# 03cpu_sodimm.net
KiCad netlist of a schematic drawn in Altium Designer
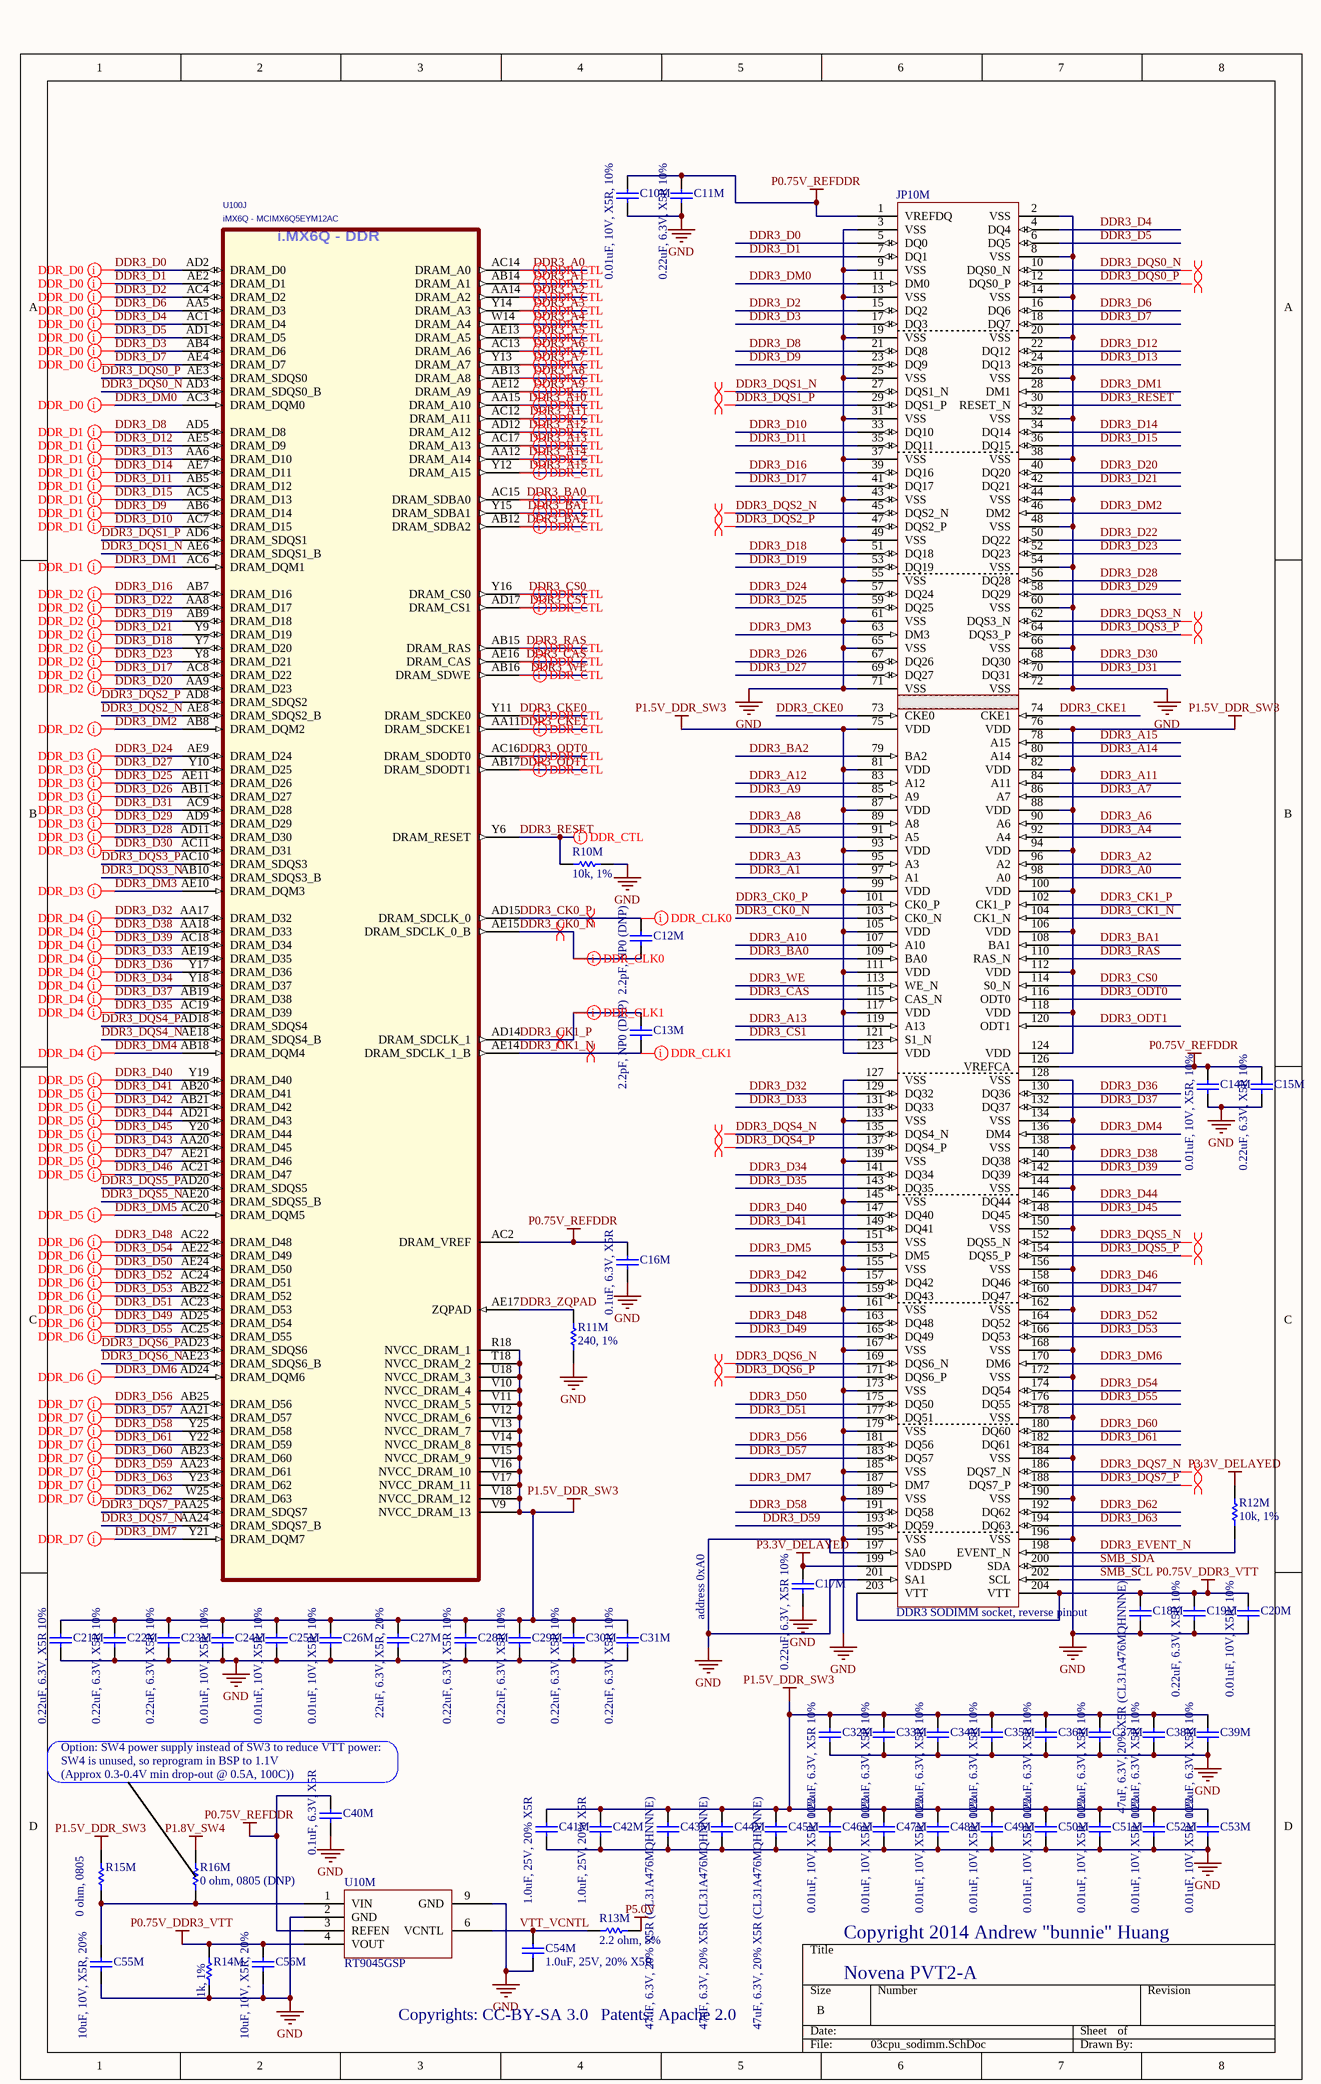
[diagram p0: 03cpu_sodimm.SchDoc]

(export (version "E")
  (design (tool "Eeschema 10.0.6"))
  (components
    (comp (ref "C10M")
      (value "0.01uF, 10V, X5R, 10%")
      (footprint "CAPC0603N_B")
      (description "Capacitor (Semiconductor SIM Model)")
      (fields (field (name "PUBLISHER") "Altium Limited"))
      (libsource (lib "Miscellaneous Devices") (part "Cap Semi"))
    )
    (comp (ref "C11M")
      (value "0.22uF, 6.3V, X5R 10%")
      (footprint "CAPC0603N_B")
      (description "CAP CER 0.22UF 6.3V 20% X5R 0201")
      (fields (field (name "PUBLISHER") "Altium Limited"))
      (libsource (lib "Miscellaneous Devices") (part "Cap Semi"))
    )
    (comp (ref "C12M")
      (value "2.2pF, NP0 (DNP)")
      (footprint "CAPC1005N")
      (description "Capacitor (Semiconductor SIM Model)")
      (fields (field (name "PUBLISHER") "Altium Limited"))
      (libsource (lib "Miscellaneous Devices") (part "Cap Semi"))
    )
    (comp (ref "C13M")
      (value "2.2pF, NP0 (DNP)")
      (footprint "CAPC1005N")
      (description "Capacitor (Semiconductor SIM Model)")
      (fields (field (name "PUBLISHER") "Altium Limited"))
      (libsource (lib "Miscellaneous Devices") (part "Cap Semi"))
    )
    (comp (ref "C14M")
      (value "0.01uF, 10V, X5R, 10%")
      (footprint "CAPC0603N_B")
      (description "Capacitor (Semiconductor SIM Model)")
      (fields (field (name "PUBLISHER") "Altium Limited"))
      (libsource (lib "Miscellaneous Devices") (part "Cap Semi"))
    )
    (comp (ref "C15M")
      (value "0.22uF, 6.3V, X5R 10%")
      (footprint "CAPC0603N_B")
      (description "CAP CER 0.22UF 6.3V 20% X5R 0201")
      (fields (field (name "PUBLISHER") "Altium Limited"))
      (libsource (lib "Miscellaneous Devices") (part "Cap Semi"))
    )
    (comp (ref "C16M")
      (value "0.1uF, 6.3V, X5R")
      (footprint "CAPC0603N_B")
      (description "Capacitor (Semiconductor SIM Model)")
      (fields (field (name "PUBLISHER") "Altium Limited"))
      (libsource (lib "Miscellaneous Devices") (part "Cap Semi"))
    )
    (comp (ref "C17M")
      (value "0.22uF, 6.3V, X5R 10%")
      (footprint "CAPC0603N_B")
      (description "CAP CER 0.22UF 6.3V 20% X5R 0201")
      (fields (field (name "PUBLISHER") "Altium Limited"))
      (libsource (lib "Miscellaneous Devices") (part "Cap Semi"))
    )
    (comp (ref "C18M")
      (value "47uF, 6.3V, 20% X5R (CL31A476MQHNNNE)")
      (footprint "CAPC3216N")
      (description "Capacitor (Semiconductor SIM Model)")
      (fields (field (name "PUBLISHER") "Altium Limited"))
      (libsource (lib "Miscellaneous Devices") (part "Cap Semi"))
    )
    (comp (ref "C19M")
      (value "0.22uF, 6.3V, X5R 10%")
      (footprint "CAPC0603N_B")
      (description "CAP CER 0.22UF 6.3V 20% X5R 0201")
      (fields (field (name "PUBLISHER") "Altium Limited"))
      (libsource (lib "Miscellaneous Devices") (part "Cap Semi"))
    )
    (comp (ref "C20M")
      (value "0.01uF, 10V, X5R, 10%")
      (footprint "CAPC0603N_B")
      (description "Capacitor (Semiconductor SIM Model)")
      (fields (field (name "PUBLISHER") "Altium Limited"))
      (libsource (lib "Miscellaneous Devices") (part "Cap Semi"))
    )
    (comp (ref "C21M")
      (value "0.22uF, 6.3V, X5R 10%")
      (footprint "CAPC0603N_B")
      (description "CAP CER 0.22UF 6.3V 20% X5R 0201")
      (fields (field (name "PUBLISHER") "Altium Limited"))
      (libsource (lib "Miscellaneous Devices") (part "Cap Semi"))
    )
    (comp (ref "C22M")
      (value "0.22uF, 6.3V, X5R 10%")
      (footprint "CAPC0603N_B")
      (description "CAP CER 0.22UF 6.3V 20% X5R 0201")
      (fields (field (name "PUBLISHER") "Altium Limited"))
      (libsource (lib "Miscellaneous Devices") (part "Cap Semi"))
    )
    (comp (ref "C23M")
      (value "0.22uF, 6.3V, X5R 10%")
      (footprint "CAPC0603N_B")
      (description "CAP CER 0.22UF 6.3V 20% X5R 0201")
      (fields (field (name "PUBLISHER") "Altium Limited"))
      (libsource (lib "Miscellaneous Devices") (part "Cap Semi"))
    )
    (comp (ref "C24M")
      (value "0.01uF, 10V, X5R, 10%")
      (footprint "CAPC0603N_B")
      (description "Capacitor (Semiconductor SIM Model)")
      (fields (field (name "PUBLISHER") "Altium Limited"))
      (libsource (lib "Miscellaneous Devices") (part "Cap Semi"))
    )
    (comp (ref "C25M")
      (value "0.01uF, 10V, X5R, 10%")
      (footprint "CAPC0603N_B")
      (description "Capacitor (Semiconductor SIM Model)")
      (fields (field (name "PUBLISHER") "Altium Limited"))
      (libsource (lib "Miscellaneous Devices") (part "Cap Semi"))
    )
    (comp (ref "C26M")
      (value "0.01uF, 10V, X5R, 10%")
      (footprint "CAPC0603N_B")
      (description "Capacitor (Semiconductor SIM Model)")
      (fields (field (name "PUBLISHER") "Altium Limited"))
      (libsource (lib "Miscellaneous Devices") (part "Cap Semi"))
    )
    (comp (ref "C27M")
      (value "22uF, 6.3V, X5R, 20%")
      (footprint "CAPC1608N_HD")
      (description "Capacitor (Semiconductor SIM Model)")
      (fields (field (name "PUBLISHER") "Altium Limited"))
      (libsource (lib "Miscellaneous Devices") (part "Cap Semi"))
    )
    (comp (ref "C28M")
      (value "0.22uF, 6.3V, X5R 10%")
      (footprint "CAPC0603N_B")
      (description "CAP CER 0.22UF 6.3V 20% X5R 0201")
      (fields (field (name "PUBLISHER") "Altium Limited"))
      (libsource (lib "Miscellaneous Devices") (part "Cap Semi"))
    )
    (comp (ref "C29M")
      (value "0.22uF, 6.3V, X5R 10%")
      (footprint "CAPC0603N_B")
      (description "CAP CER 0.22UF 6.3V 20% X5R 0201")
      (fields (field (name "PUBLISHER") "Altium Limited"))
      (libsource (lib "Miscellaneous Devices") (part "Cap Semi"))
    )
    (comp (ref "C30M")
      (value "0.22uF, 6.3V, X5R 10%")
      (footprint "CAPC0603N_B")
      (description "CAP CER 0.22UF 6.3V 20% X5R 0201")
      (fields (field (name "PUBLISHER") "Altium Limited"))
      (libsource (lib "Miscellaneous Devices") (part "Cap Semi"))
    )
    (comp (ref "C31M")
      (value "0.22uF, 6.3V, X5R 10%")
      (footprint "CAPC0603N_B")
      (description "CAP CER 0.22UF 6.3V 20% X5R 0201")
      (fields (field (name "PUBLISHER") "Altium Limited"))
      (libsource (lib "Miscellaneous Devices") (part "Cap Semi"))
    )
    (comp (ref "C32M")
      (value "0.22uF, 6.3V, X5R 10%")
      (footprint "CAPC0603N_B")
      (description "CAP CER 0.22UF 6.3V 20% X5R 0201")
      (fields (field (name "PUBLISHER") "Altium Limited"))
      (libsource (lib "Miscellaneous Devices") (part "Cap Semi"))
    )
    (comp (ref "C33M")
      (value "0.22uF, 6.3V, X5R 10%")
      (footprint "CAPC0603N_B")
      (description "CAP CER 0.22UF 6.3V 20% X5R 0201")
      (fields (field (name "PUBLISHER") "Altium Limited"))
      (libsource (lib "Miscellaneous Devices") (part "Cap Semi"))
    )
    (comp (ref "C34M")
      (value "0.22uF, 6.3V, X5R 10%")
      (footprint "CAPC0603N_B")
      (description "CAP CER 0.22UF 6.3V 20% X5R 0201")
      (fields (field (name "PUBLISHER") "Altium Limited"))
      (libsource (lib "Miscellaneous Devices") (part "Cap Semi"))
    )
    (comp (ref "C35M")
      (value "0.22uF, 6.3V, X5R 10%")
      (footprint "CAPC0603N_B")
      (description "CAP CER 0.22UF 6.3V 20% X5R 0201")
      (fields (field (name "PUBLISHER") "Altium Limited"))
      (libsource (lib "Miscellaneous Devices") (part "Cap Semi"))
    )
    (comp (ref "C36M")
      (value "0.22uF, 6.3V, X5R 10%")
      (footprint "CAPC0603N_B")
      (description "CAP CER 0.22UF 6.3V 20% X5R 0201")
      (fields (field (name "PUBLISHER") "Altium Limited"))
      (libsource (lib "Miscellaneous Devices") (part "Cap Semi"))
    )
    (comp (ref "C37M")
      (value "0.22uF, 6.3V, X5R 10%")
      (footprint "CAPC0603N_B")
      (description "CAP CER 0.22UF 6.3V 20% X5R 0201")
      (fields (field (name "PUBLISHER") "Altium Limited"))
      (libsource (lib "Miscellaneous Devices") (part "Cap Semi"))
    )
    (comp (ref "C38M")
      (value "0.22uF, 6.3V, X5R 10%")
      (footprint "CAPC0603N_B")
      (description "CAP CER 0.22UF 6.3V 20% X5R 0201")
      (fields (field (name "PUBLISHER") "Altium Limited"))
      (libsource (lib "Miscellaneous Devices") (part "Cap Semi"))
    )
    (comp (ref "C39M")
      (value "0.22uF, 6.3V, X5R 10%")
      (footprint "CAPC0603N_B")
      (description "CAP CER 0.22UF 6.3V 20% X5R 0201")
      (fields (field (name "PUBLISHER") "Altium Limited"))
      (libsource (lib "Miscellaneous Devices") (part "Cap Semi"))
    )
    (comp (ref "C40M")
      (value "0.1uF, 6.3V, X5R")
      (footprint "CAPC0603N_B")
      (description "Capacitor (Semiconductor SIM Model)")
      (fields (field (name "PUBLISHER") "Altium Limited"))
      (libsource (lib "Miscellaneous Devices") (part "Cap Semi"))
    )
    (comp (ref "C41M")
      (value "1.0uF, 25V, 20% X5R")
      (footprint "CAPC1608N")
      (description "Capacitor (Semiconductor SIM Model)")
      (fields (field (name "PUBLISHER") "Altium Limited"))
      (libsource (lib "Miscellaneous Devices") (part "Cap Semi"))
    )
    (comp (ref "C42M")
      (value "1.0uF, 25V, 20% X5R")
      (footprint "CAPC1608N")
      (description "Capacitor (Semiconductor SIM Model)")
      (fields (field (name "PUBLISHER") "Altium Limited"))
      (libsource (lib "Miscellaneous Devices") (part "Cap Semi"))
    )
    (comp (ref "C43M")
      (value "47uF, 6.3V, 20% X5R (CL31A476MQHNNNE)")
      (footprint "CAPC3216N")
      (description "Capacitor (Semiconductor SIM Model)")
      (fields (field (name "PUBLISHER") "Altium Limited"))
      (libsource (lib "Miscellaneous Devices") (part "Cap Semi"))
    )
    (comp (ref "C44M")
      (value "47uF, 6.3V, 20% X5R (CL31A476MQHNNNE)")
      (footprint "CAPC3216N")
      (description "Capacitor (Semiconductor SIM Model)")
      (fields (field (name "PUBLISHER") "Altium Limited"))
      (libsource (lib "Miscellaneous Devices") (part "Cap Semi"))
    )
    (comp (ref "C45M")
      (value "47uF, 6.3V, 20% X5R (CL31A476MQHNNNE)")
      (footprint "CAPC3216N")
      (description "Capacitor (Semiconductor SIM Model)")
      (fields (field (name "PUBLISHER") "Altium Limited"))
      (libsource (lib "Miscellaneous Devices") (part "Cap Semi"))
    )
    (comp (ref "C46M")
      (value "0.01uF, 10V, X5R, 10%")
      (footprint "CAPC0603N_B")
      (description "Capacitor (Semiconductor SIM Model)")
      (fields (field (name "PUBLISHER") "Altium Limited"))
      (libsource (lib "Miscellaneous Devices") (part "Cap Semi"))
    )
    (comp (ref "C47M")
      (value "0.01uF, 10V, X5R, 10%")
      (footprint "CAPC0603N_B")
      (description "Capacitor (Semiconductor SIM Model)")
      (fields (field (name "PUBLISHER") "Altium Limited"))
      (libsource (lib "Miscellaneous Devices") (part "Cap Semi"))
    )
    (comp (ref "C48M")
      (value "0.01uF, 10V, X5R, 10%")
      (footprint "CAPC0603N_B")
      (description "Capacitor (Semiconductor SIM Model)")
      (fields (field (name "PUBLISHER") "Altium Limited"))
      (libsource (lib "Miscellaneous Devices") (part "Cap Semi"))
    )
    (comp (ref "C49M")
      (value "0.01uF, 10V, X5R, 10%")
      (footprint "CAPC0603N_B")
      (description "Capacitor (Semiconductor SIM Model)")
      (fields (field (name "PUBLISHER") "Altium Limited"))
      (libsource (lib "Miscellaneous Devices") (part "Cap Semi"))
    )
    (comp (ref "C50M")
      (value "0.01uF, 10V, X5R, 10%")
      (footprint "CAPC0603N_B")
      (description "Capacitor (Semiconductor SIM Model)")
      (fields (field (name "PUBLISHER") "Altium Limited"))
      (libsource (lib "Miscellaneous Devices") (part "Cap Semi"))
    )
    (comp (ref "C51M")
      (value "0.01uF, 10V, X5R, 10%")
      (footprint "CAPC0603N_B")
      (description "Capacitor (Semiconductor SIM Model)")
      (fields (field (name "PUBLISHER") "Altium Limited"))
      (libsource (lib "Miscellaneous Devices") (part "Cap Semi"))
    )
    (comp (ref "C52M")
      (value "0.01uF, 10V, X5R, 10%")
      (footprint "CAPC0603N_B")
      (description "Capacitor (Semiconductor SIM Model)")
      (fields (field (name "PUBLISHER") "Altium Limited"))
      (libsource (lib "Miscellaneous Devices") (part "Cap Semi"))
    )
    (comp (ref "C53M")
      (value "0.01uF, 10V, X5R, 10%")
      (footprint "CAPC0603N_B")
      (description "Capacitor (Semiconductor SIM Model)")
      (fields (field (name "PUBLISHER") "Altium Limited"))
      (libsource (lib "Miscellaneous Devices") (part "Cap Semi"))
    )
    (comp (ref "C54M")
      (value "1.0uF, 25V, 20% X5R")
      (footprint "CAPC1608N")
      (description "Capacitor (Semiconductor SIM Model)")
      (fields (field (name "PUBLISHER") "Altium Limited"))
      (libsource (lib "Miscellaneous Devices") (part "Cap Semi"))
    )
    (comp (ref "C55M")
      (value "10uF, 10V, X5R, 20%")
      (footprint "CAPC1608N")
      (description "Capacitor (Semiconductor SIM Model)")
      (fields (field (name "PUBLISHER") "Altium Limited"))
      (libsource (lib "Miscellaneous Devices") (part "Cap Semi"))
    )
    (comp (ref "C56M")
      (value "10uF, 10V, X5R, 20%")
      (footprint "CAPC1608N")
      (description "Capacitor (Semiconductor SIM Model)")
      (fields (field (name "PUBLISHER") "Altium Limited"))
      (libsource (lib "Miscellaneous Devices") (part "Cap Semi"))
    )
    (comp (ref "JP10M")
      (value "DDR3 SODIMM socket, reverse pinout")
      (footprint "DDR3_SODIMM_REV")
      (description "TE Connectivity 2013311 or equiv (9.2mm height)")
      (libsource (lib "commonsch") (part "DDR3_SODIMM"))
    )
    (comp (ref "R10M")
      (value "10k, 1%")
      (footprint "RESC1005N")
      (description "Resistor")
      (fields (field (name "PUBLISHER") "Altium Limited"))
      (libsource (lib "Miscellaneous Devices") (part "Res1"))
    )
    (comp (ref "R11M")
      (value "240, 1%")
      (footprint "RESC1005N")
      (description "Resistor")
      (fields (field (name "PUBLISHER") "Altium Limited"))
      (libsource (lib "Miscellaneous Devices") (part "Res1"))
    )
    (comp (ref "R12M")
      (value "10k, 1%")
      (footprint "RESC1005N")
      (description "Resistor")
      (fields (field (name "PUBLISHER") "Altium Limited"))
      (libsource (lib "Miscellaneous Devices") (part "Res1"))
    )
    (comp (ref "R13M")
      (value "2.2 ohm, 5%")
      (footprint "RESC1005N")
      (description "Resistor")
      (fields (field (name "PUBLISHER") "Altium Limited"))
      (libsource (lib "Miscellaneous Devices") (part "Res1"))
    )
    (comp (ref "R14M")
      (value "1k, 1%")
      (footprint "RESC1005N")
      (description "Resistor")
      (fields (field (name "PUBLISHER") "Altium Limited"))
      (libsource (lib "Miscellaneous Devices") (part "Res1"))
    )
    (comp (ref "R15M")
      (value "0 ohm, 0805")
      (footprint "RESC2012N")
      (description "Resistor")
      (fields (field (name "PUBLISHER") "Altium Limited"))
      (libsource (lib "Miscellaneous Devices") (part "Res1"))
    )
    (comp (ref "R16M")
      (value "0 ohm, 0805 (DNP)")
      (footprint "RESC2012N")
      (description "Resistor")
      (fields (field (name "PUBLISHER") "Altium Limited"))
      (libsource (lib "Miscellaneous Devices") (part "Res1"))
    )
    (comp (ref "U10M")
      (value "RT9045GSP")
      (footprint "SOIC127P600_HS-8N")
      (description "1.8A sink/source bus termination regulator (VTT)")
      (libsource (lib "commonsch") (part "RT9045GSP"))
    )
    (comp (ref "U100")
      (value "iMX6Q - MCIMX6Q5EYM12AC")
      (description "PCIMX6Q5EVT10AC")
      (libsource (lib "*") (part "PCIMX6Q6VV1A"))
    )
  )
  (nets
    (net (code "1") (name "/DDR3_A0") (class "Default")
      (node (ref "JP10M") (pin "98") (pinfunction "A0_98") (pintype "input"))
      (node (ref "U100") (pin "AC14") (pinfunction "DRAM_A0_AC14") (pintype "output"))
    )
    (net (code "2") (name "/DDR3_A1") (class "Default")
      (node (ref "JP10M") (pin "97") (pinfunction "A1_97") (pintype "input"))
      (node (ref "U100") (pin "AB14") (pinfunction "DRAM_A1_AB14") (pintype "output"))
    )
    (net (code "3") (name "/DDR3_A2") (class "Default")
      (node (ref "JP10M") (pin "96") (pinfunction "A2_96") (pintype "input"))
      (node (ref "U100") (pin "AA14") (pinfunction "DRAM_A2_AA14") (pintype "output"))
    )
    (net (code "4") (name "/DDR3_A3") (class "Default")
      (node (ref "JP10M") (pin "95") (pinfunction "A3_95") (pintype "input"))
      (node (ref "U100") (pin "Y14") (pinfunction "DRAM_A3_Y14") (pintype "output"))
    )
    (net (code "5") (name "/DDR3_A4") (class "Default")
      (node (ref "JP10M") (pin "92") (pinfunction "A4_92") (pintype "input"))
      (node (ref "U100") (pin "W14") (pinfunction "DRAM_A4_W14") (pintype "output"))
    )
    (net (code "6") (name "/DDR3_A5") (class "Default")
      (node (ref "JP10M") (pin "91") (pinfunction "A5_91") (pintype "input"))
      (node (ref "U100") (pin "AE13") (pinfunction "DRAM_A5_AE13") (pintype "output"))
    )
    (net (code "7") (name "/DDR3_A6") (class "Default")
      (node (ref "JP10M") (pin "90") (pinfunction "A6_90") (pintype "input"))
      (node (ref "U100") (pin "AC13") (pinfunction "DRAM_A6_AC13") (pintype "output"))
    )
    (net (code "8") (name "/DDR3_A7") (class "Default")
      (node (ref "JP10M") (pin "86") (pinfunction "A7_86") (pintype "input"))
      (node (ref "U100") (pin "Y13") (pinfunction "DRAM_A7_Y13") (pintype "output"))
    )
    (net (code "9") (name "/DDR3_A8") (class "Default")
      (node (ref "JP10M") (pin "89") (pinfunction "A8_89") (pintype "input"))
      (node (ref "U100") (pin "AB13") (pinfunction "DRAM_A8_AB13") (pintype "output"))
    )
    (net (code "10") (name "/DDR3_A9") (class "Default")
      (node (ref "JP10M") (pin "85") (pinfunction "A9_85") (pintype "input"))
      (node (ref "U100") (pin "AE12") (pinfunction "DRAM_A9_AE12") (pintype "output"))
    )
    (net (code "11") (name "/DDR3_A10") (class "Default")
      (node (ref "JP10M") (pin "107") (pinfunction "A10_107") (pintype "input"))
      (node (ref "U100") (pin "AA15") (pinfunction "DRAM_A10_AA15") (pintype "output"))
    )
    (net (code "12") (name "/DDR3_A11") (class "Default")
      (node (ref "JP10M") (pin "84") (pinfunction "A11_84") (pintype "input"))
      (node (ref "U100") (pin "AC12") (pinfunction "DRAM_A11_AC12") (pintype "output"))
    )
    (net (code "13") (name "/DDR3_A12") (class "Default")
      (node (ref "JP10M") (pin "83") (pinfunction "A12_83") (pintype "input"))
      (node (ref "U100") (pin "AD12") (pinfunction "DRAM_A12_AD12") (pintype "output"))
    )
    (net (code "14") (name "/DDR3_A13") (class "Default")
      (node (ref "JP10M") (pin "119") (pinfunction "A13_119") (pintype "input"))
      (node (ref "U100") (pin "AC17") (pinfunction "DRAM_A13_AC17") (pintype "output"))
    )
    (net (code "15") (name "/DDR3_A14") (class "Default")
      (node (ref "JP10M") (pin "80") (pinfunction "A14_80") (pintype "input"))
      (node (ref "U100") (pin "AA12") (pinfunction "DRAM_A14_AA12") (pintype "output"))
    )
    (net (code "16") (name "/DDR3_A15") (class "Default")
      (node (ref "JP10M") (pin "78") (pinfunction "A15_78") (pintype "input"))
      (node (ref "U100") (pin "Y12") (pinfunction "DRAM_A15_Y12") (pintype "output"))
    )
    (net (code "17") (name "/DDR3_BA0") (class "Default")
      (node (ref "JP10M") (pin "109") (pinfunction "BA0_109") (pintype "input"))
      (node (ref "U100") (pin "AC15") (pinfunction "DRAM_SDBA0_AC15") (pintype "output"))
    )
    (net (code "18") (name "/DDR3_BA1") (class "Default")
      (node (ref "JP10M") (pin "108") (pinfunction "BA1_108") (pintype "input"))
      (node (ref "U100") (pin "Y15") (pinfunction "DRAM_SDBA1_Y15") (pintype "output"))
    )
    (net (code "19") (name "/DDR3_BA2") (class "Default")
      (node (ref "JP10M") (pin "79") (pinfunction "BA2_79") (pintype "input"))
      (node (ref "U100") (pin "AB12") (pinfunction "DRAM_SDBA2_AB12") (pintype "output"))
    )
    (net (code "20") (name "/DDR3_CAS") (class "Default")
      (node (ref "JP10M") (pin "115") (pinfunction "CAS_N_115") (pintype "input"))
      (node (ref "U100") (pin "AE16") (pinfunction "DRAM_CAS_AE16") (pintype "output"))
    )
    (net (code "21") (name "/DDR3_CK0_N") (class "Default")
      (node (ref "C12M") (pin "2") (pinfunction "2_2") (pintype "passive"))
      (node (ref "JP10M") (pin "103") (pinfunction "CK0_N_103") (pintype "input"))
      (node (ref "U100") (pin "AE15") (pinfunction "DRAM_SDCLK_0_B_AE15") (pintype "output"))
    )
    (net (code "22") (name "/DDR3_CK0_P") (class "Default")
      (node (ref "C12M") (pin "1") (pinfunction "1_1") (pintype "passive"))
      (node (ref "JP10M") (pin "101") (pinfunction "CK0_P_101") (pintype "input"))
      (node (ref "U100") (pin "AD15") (pinfunction "DRAM_SDCLK_0_AD15") (pintype "output"))
    )
    (net (code "23") (name "/DDR3_CK1_N") (class "Default")
      (node (ref "C13M") (pin "2") (pinfunction "2_2") (pintype "passive"))
      (node (ref "JP10M") (pin "104") (pinfunction "CK1_N_104") (pintype "input"))
      (node (ref "U100") (pin "AE14") (pinfunction "DRAM_SDCLK_1_B_AE14") (pintype "output"))
    )
    (net (code "24") (name "/DDR3_CK1_P") (class "Default")
      (node (ref "C13M") (pin "1") (pinfunction "1_1") (pintype "passive"))
      (node (ref "JP10M") (pin "102") (pinfunction "CK1_P_102") (pintype "input"))
      (node (ref "U100") (pin "AD14") (pinfunction "DRAM_SDCLK_1_AD14") (pintype "output"))
    )
    (net (code "25") (name "/DDR3_CKE0") (class "Default")
      (node (ref "JP10M") (pin "73") (pinfunction "CKE0_73") (pintype "input"))
      (node (ref "U100") (pin "Y11") (pinfunction "DRAM_SDCKE0_Y11") (pintype "output"))
    )
    (net (code "26") (name "/DDR3_CKE1") (class "Default")
      (node (ref "JP10M") (pin "74") (pinfunction "CKE1_74") (pintype "input"))
      (node (ref "U100") (pin "AA11") (pinfunction "DRAM_SDCKE1_AA11") (pintype "output"))
    )
    (net (code "27") (name "/DDR3_CS0") (class "Default")
      (node (ref "JP10M") (pin "114") (pinfunction "S0_N_114") (pintype "input"))
      (node (ref "U100") (pin "Y16") (pinfunction "DRAM_CS0_Y16") (pintype "output"))
    )
    (net (code "28") (name "/DDR3_CS1") (class "Default")
      (node (ref "JP10M") (pin "121") (pinfunction "S1_N_121") (pintype "input"))
      (node (ref "U100") (pin "AD17") (pinfunction "DRAM_CS1_AD17") (pintype "output"))
    )
    (net (code "29") (name "/DDR3_D0") (class "Default")
      (node (ref "JP10M") (pin "5") (pinfunction "DQ0_5") (pintype "bidirectional"))
      (node (ref "U100") (pin "AD2") (pinfunction "DRAM_D0_AD2") (pintype "bidirectional"))
    )
    (net (code "30") (name "/DDR3_D1") (class "Default")
      (node (ref "JP10M") (pin "7") (pinfunction "DQ1_7") (pintype "bidirectional"))
      (node (ref "U100") (pin "AE2") (pinfunction "DRAM_D1_AE2") (pintype "bidirectional"))
    )
    (net (code "31") (name "/DDR3_D2") (class "Default")
      (node (ref "JP10M") (pin "15") (pinfunction "DQ2_15") (pintype "bidirectional"))
      (node (ref "U100") (pin "AC4") (pinfunction "DRAM_D2_AC4") (pintype "bidirectional"))
    )
    (net (code "32") (name "/DDR3_D3") (class "Default")
      (node (ref "JP10M") (pin "17") (pinfunction "DQ3_17") (pintype "bidirectional"))
      (node (ref "U100") (pin "AB4") (pinfunction "DRAM_D6_AB4") (pintype "bidirectional"))
    )
    (net (code "33") (name "/DDR3_D4") (class "Default")
      (node (ref "JP10M") (pin "4") (pinfunction "DQ4_4") (pintype "bidirectional"))
      (node (ref "U100") (pin "AC1") (pinfunction "DRAM_D4_AC1") (pintype "bidirectional"))
    )
    (net (code "34") (name "/DDR3_D5") (class "Default")
      (node (ref "JP10M") (pin "6") (pinfunction "DQ5_6") (pintype "bidirectional"))
      (node (ref "U100") (pin "AD1") (pinfunction "DRAM_D5_AD1") (pintype "bidirectional"))
    )
    (net (code "35") (name "/DDR3_D6") (class "Default")
      (node (ref "JP10M") (pin "16") (pinfunction "DQ6_16") (pintype "bidirectional"))
      (node (ref "U100") (pin "AA5") (pinfunction "DRAM_D3_AA5") (pintype "bidirectional"))
    )
    (net (code "36") (name "/DDR3_D7") (class "Default")
      (node (ref "JP10M") (pin "18") (pinfunction "DQ7_18") (pintype "bidirectional"))
      (node (ref "U100") (pin "AE4") (pinfunction "DRAM_D7_AE4") (pintype "bidirectional"))
    )
    (net (code "37") (name "/DDR3_D8") (class "Default")
      (node (ref "JP10M") (pin "21") (pinfunction "DQ8_21") (pintype "bidirectional"))
      (node (ref "U100") (pin "AD5") (pinfunction "DRAM_D8_AD5") (pintype "bidirectional"))
    )
    (net (code "38") (name "/DDR3_D9") (class "Default")
      (node (ref "JP10M") (pin "23") (pinfunction "DQ9_23") (pintype "bidirectional"))
      (node (ref "U100") (pin "AB6") (pinfunction "DRAM_D14_AB6") (pintype "bidirectional"))
    )
    (net (code "39") (name "/DDR3_D10") (class "Default")
      (node (ref "JP10M") (pin "33") (pinfunction "DQ10_33") (pintype "bidirectional"))
      (node (ref "U100") (pin "AC7") (pinfunction "DRAM_D15_AC7") (pintype "bidirectional"))
    )
    (net (code "40") (name "/DDR3_D11") (class "Default")
      (node (ref "JP10M") (pin "35") (pinfunction "DQ11_35") (pintype "bidirectional"))
      (node (ref "U100") (pin "AB5") (pinfunction "DRAM_D12_AB5") (pintype "bidirectional"))
    )
    (net (code "41") (name "/DDR3_D12") (class "Default")
      (node (ref "JP10M") (pin "22") (pinfunction "DQ12_22") (pintype "bidirectional"))
      (node (ref "U100") (pin "AE5") (pinfunction "DRAM_D9_AE5") (pintype "bidirectional"))
    )
    (net (code "42") (name "/DDR3_D13") (class "Default")
      (node (ref "JP10M") (pin "24") (pinfunction "DQ13_24") (pintype "bidirectional"))
      (node (ref "U100") (pin "AA6") (pinfunction "DRAM_D10_AA6") (pintype "bidirectional"))
    )
    (net (code "43") (name "/DDR3_D14") (class "Default")
      (node (ref "JP10M") (pin "34") (pinfunction "DQ14_34") (pintype "bidirectional"))
      (node (ref "U100") (pin "AE7") (pinfunction "DRAM_D11_AE7") (pintype "bidirectional"))
    )
    (net (code "44") (name "/DDR3_D15") (class "Default")
      (node (ref "JP10M") (pin "36") (pinfunction "DQ15_36") (pintype "bidirectional"))
      (node (ref "U100") (pin "AC5") (pinfunction "DRAM_D13_AC5") (pintype "bidirectional"))
    )
    (net (code "45") (name "/DDR3_D16") (class "Default")
      (node (ref "JP10M") (pin "39") (pinfunction "DQ16_39") (pintype "bidirectional"))
      (node (ref "U100") (pin "AB7") (pinfunction "DRAM_D16_AB7") (pintype "bidirectional"))
    )
    (net (code "46") (name "/DDR3_D17") (class "Default")
      (node (ref "JP10M") (pin "41") (pinfunction "DQ17_41") (pintype "bidirectional"))
      (node (ref "U100") (pin "AC8") (pinfunction "DRAM_D22_AC8") (pintype "bidirectional"))
    )
    (net (code "47") (name "/DDR3_D18") (class "Default")
      (node (ref "JP10M") (pin "51") (pinfunction "DQ18_51") (pintype "bidirectional"))
      (node (ref "U100") (pin "Y7") (pinfunction "DRAM_D20_Y7") (pintype "bidirectional"))
    )
    (net (code "48") (name "/DDR3_D19") (class "Default")
      (node (ref "JP10M") (pin "53") (pinfunction "DQ19_53") (pintype "bidirectional"))
      (node (ref "U100") (pin "AB9") (pinfunction "DRAM_D18_AB9") (pintype "bidirectional"))
    )
    (net (code "49") (name "/DDR3_D20") (class "Default")
      (node (ref "JP10M") (pin "40") (pinfunction "DQ20_40") (pintype "bidirectional"))
      (node (ref "U100") (pin "AA9") (pinfunction "DRAM_D23_AA9") (pintype "bidirectional"))
    )
    (net (code "50") (name "/DDR3_D21") (class "Default")
      (node (ref "JP10M") (pin "42") (pinfunction "DQ21_42") (pintype "bidirectional"))
      (node (ref "U100") (pin "Y9") (pinfunction "DRAM_D19_Y9") (pintype "bidirectional"))
    )
    (net (code "51") (name "/DDR3_D22") (class "Default")
      (node (ref "JP10M") (pin "50") (pinfunction "DQ22_50") (pintype "bidirectional"))
      (node (ref "U100") (pin "AA8") (pinfunction "DRAM_D17_AA8") (pintype "bidirectional"))
    )
    (net (code "52") (name "/DDR3_D23") (class "Default")
      (node (ref "JP10M") (pin "52") (pinfunction "DQ23_52") (pintype "bidirectional"))
      (node (ref "U100") (pin "Y8") (pinfunction "DRAM_D21_Y8") (pintype "bidirectional"))
    )
    (net (code "53") (name "/DDR3_D24") (class "Default")
      (node (ref "JP10M") (pin "57") (pinfunction "DQ24_57") (pintype "bidirectional"))
      (node (ref "U100") (pin "AE9") (pinfunction "DRAM_D24_AE9") (pintype "bidirectional"))
    )
    (net (code "54") (name "/DDR3_D25") (class "Default")
      (node (ref "JP10M") (pin "59") (pinfunction "DQ25_59") (pintype "bidirectional"))
      (node (ref "U100") (pin "AE11") (pinfunction "DRAM_D26_AE11") (pintype "bidirectional"))
    )
    (net (code "55") (name "/DDR3_D26") (class "Default")
      (node (ref "JP10M") (pin "67") (pinfunction "DQ26_67") (pintype "bidirectional"))
      (node (ref "U100") (pin "AB11") (pinfunction "DRAM_D27_AB11") (pintype "bidirectional"))
    )
    (net (code "56") (name "/DDR3_D27") (class "Default")
      (node (ref "JP10M") (pin "69") (pinfunction "DQ27_69") (pintype "bidirectional"))
      (node (ref "U100") (pin "Y10") (pinfunction "DRAM_D25_Y10") (pintype "bidirectional"))
    )
    (net (code "57") (name "/DDR3_D28") (class "Default")
      (node (ref "JP10M") (pin "56") (pinfunction "DQ28_56") (pintype "bidirectional"))
      (node (ref "U100") (pin "AD11") (pinfunction "DRAM_D30_AD11") (pintype "bidirectional"))
    )
    (net (code "58") (name "/DDR3_D29") (class "Default")
      (node (ref "JP10M") (pin "58") (pinfunction "DQ29_58") (pintype "bidirectional"))
      (node (ref "U100") (pin "AD9") (pinfunction "DRAM_D29_AD9") (pintype "bidirectional"))
    )
    (net (code "59") (name "/DDR3_D30") (class "Default")
      (node (ref "JP10M") (pin "68") (pinfunction "DQ30_68") (pintype "bidirectional"))
      (node (ref "U100") (pin "AC11") (pinfunction "DRAM_D31_AC11") (pintype "bidirectional"))
    )
    (net (code "60") (name "/DDR3_D31") (class "Default")
      (node (ref "JP10M") (pin "70") (pinfunction "DQ31_70") (pintype "bidirectional"))
      (node (ref "U100") (pin "AC9") (pinfunction "DRAM_D28_AC9") (pintype "bidirectional"))
    )
    (net (code "61") (name "/DDR3_D32") (class "Default")
      (node (ref "JP10M") (pin "129") (pinfunction "DQ32_129") (pintype "bidirectional"))
      (node (ref "U100") (pin "AA17") (pinfunction "DRAM_D32_AA17") (pintype "bidirectional"))
    )
    (net (code "62") (name "/DDR3_D33") (class "Default")
      (node (ref "JP10M") (pin "131") (pinfunction "DQ33_131") (pintype "bidirectional"))
      (node (ref "U100") (pin "AE19") (pinfunction "DRAM_D35_AE19") (pintype "bidirectional"))
    )
    (net (code "63") (name "/DDR3_D34") (class "Default")
      (node (ref "JP10M") (pin "141") (pinfunction "DQ34_141") (pintype "bidirectional"))
      (node (ref "U100") (pin "Y18") (pinfunction "DRAM_D37_Y18") (pintype "bidirectional"))
    )
    (net (code "64") (name "/DDR3_D35") (class "Default")
      (node (ref "JP10M") (pin "143") (pinfunction "DQ35_143") (pintype "bidirectional"))
      (node (ref "U100") (pin "AC19") (pinfunction "DRAM_D39_AC19") (pintype "bidirectional"))
    )
    (net (code "65") (name "/DDR3_D36") (class "Default")
      (node (ref "JP10M") (pin "130") (pinfunction "DQ36_130") (pintype "bidirectional"))
      (node (ref "U100") (pin "Y17") (pinfunction "DRAM_D36_Y17") (pintype "bidirectional"))
    )
    (net (code "66") (name "/DDR3_D37") (class "Default")
      (node (ref "JP10M") (pin "132") (pinfunction "DQ37_132") (pintype "bidirectional"))
      (node (ref "U100") (pin "AB19") (pinfunction "DRAM_D38_AB19") (pintype "bidirectional"))
    )
    (net (code "67") (name "/DDR3_D38") (class "Default")
      (node (ref "JP10M") (pin "140") (pinfunction "DQ38_140") (pintype "bidirectional"))
      (node (ref "U100") (pin "AA18") (pinfunction "DRAM_D33_AA18") (pintype "bidirectional"))
    )
    (net (code "68") (name "/DDR3_D39") (class "Default")
      (node (ref "JP10M") (pin "142") (pinfunction "DQ39_142") (pintype "bidirectional"))
      (node (ref "U100") (pin "AC18") (pinfunction "DRAM_D34_AC18") (pintype "bidirectional"))
    )
    (net (code "69") (name "/DDR3_D40") (class "Default")
      (node (ref "JP10M") (pin "147") (pinfunction "DQ40_147") (pintype "bidirectional"))
      (node (ref "U100") (pin "Y19") (pinfunction "DRAM_D40_Y19") (pintype "bidirectional"))
    )
    (net (code "70") (name "/DDR3_D41") (class "Default")
      (node (ref "JP10M") (pin "149") (pinfunction "DQ41_149") (pintype "bidirectional"))
      (node (ref "U100") (pin "AB20") (pinfunction "DRAM_D41_AB20") (pintype "bidirectional"))
    )
    (net (code "71") (name "/DDR3_D42") (class "Default")
      (node (ref "JP10M") (pin "157") (pinfunction "DQ42_157") (pintype "bidirectional"))
      (node (ref "U100") (pin "AB21") (pinfunction "DRAM_D42_AB21") (pintype "bidirectional"))
    )
    (net (code "72") (name "/DDR3_D43") (class "Default")
      (node (ref "JP10M") (pin "159") (pinfunction "DQ43_159") (pintype "bidirectional"))
      (node (ref "U100") (pin "AA20") (pinfunction "DRAM_D45_AA20") (pintype "bidirectional"))
    )
    (net (code "73") (name "/DDR3_D44") (class "Default")
      (node (ref "JP10M") (pin "146") (pinfunction "DQ44_146") (pintype "bidirectional"))
      (node (ref "U100") (pin "AD21") (pinfunction "DRAM_D43_AD21") (pintype "bidirectional"))
    )
    (net (code "74") (name "/DDR3_D45") (class "Default")
      (node (ref "JP10M") (pin "148") (pinfunction "DQ45_148") (pintype "bidirectional"))
      (node (ref "U100") (pin "Y20") (pinfunction "DRAM_D44_Y20") (pintype "bidirectional"))
    )
    (net (code "75") (name "/DDR3_D46") (class "Default")
      (node (ref "JP10M") (pin "158") (pinfunction "DQ46_158") (pintype "bidirectional"))
      (node (ref "U100") (pin "AC21") (pinfunction "DRAM_D47_AC21") (pintype "bidirectional"))
    )
    (net (code "76") (name "/DDR3_D47") (class "Default")
      (node (ref "JP10M") (pin "160") (pinfunction "DQ47_160") (pintype "bidirectional"))
      (node (ref "U100") (pin "AE21") (pinfunction "DRAM_D46_AE21") (pintype "bidirectional"))
    )
    (net (code "77") (name "/DDR3_D48") (class "Default")
      (node (ref "JP10M") (pin "163") (pinfunction "DQ48_163") (pintype "bidirectional"))
      (node (ref "U100") (pin "AC22") (pinfunction "DRAM_D48_AC22") (pintype "bidirectional"))
    )
    (net (code "78") (name "/DDR3_D49") (class "Default")
      (node (ref "JP10M") (pin "165") (pinfunction "DQ49_165") (pintype "bidirectional"))
      (node (ref "U100") (pin "AD25") (pinfunction "DRAM_D54_AD25") (pintype "bidirectional"))
    )
    (net (code "79") (name "/DDR3_D50") (class "Default")
      (node (ref "JP10M") (pin "175") (pinfunction "DQ50_175") (pintype "bidirectional"))
      (node (ref "U100") (pin "AE24") (pinfunction "DRAM_D50_AE24") (pintype "bidirectional"))
    )
    (net (code "80") (name "/DDR3_D51") (class "Default")
      (node (ref "JP10M") (pin "177") (pinfunction "DQ51_177") (pintype "bidirectional"))
      (node (ref "U100") (pin "AC23") (pinfunction "DRAM_D53_AC23") (pintype "bidirectional"))
    )
    (net (code "81") (name "/DDR3_D52") (class "Default")
      (node (ref "JP10M") (pin "164") (pinfunction "DQ52_164") (pintype "bidirectional"))
      (node (ref "U100") (pin "AC24") (pinfunction "DRAM_D51_AC24") (pintype "bidirectional"))
    )
    (net (code "82") (name "/DDR3_D53") (class "Default")
      (node (ref "JP10M") (pin "166") (pinfunction "DQ53_166") (pintype "bidirectional"))
      (node (ref "U100") (pin "AB22") (pinfunction "DRAM_D52_AB22") (pintype "bidirectional"))
    )
    (net (code "83") (name "/DDR3_D54") (class "Default")
      (node (ref "JP10M") (pin "174") (pinfunction "DQ54_174") (pintype "bidirectional"))
      (node (ref "U100") (pin "AE22") (pinfunction "DRAM_D49_AE22") (pintype "bidirectional"))
    )
    (net (code "84") (name "/DDR3_D55") (class "Default")
      (node (ref "JP10M") (pin "176") (pinfunction "DQ55_176") (pintype "bidirectional"))
      (node (ref "U100") (pin "AC25") (pinfunction "DRAM_D55_AC25") (pintype "bidirectional"))
    )
    (net (code "85") (name "/DDR3_D56") (class "Default")
      (node (ref "JP10M") (pin "181") (pinfunction "DQ56_181") (pintype "bidirectional"))
      (node (ref "U100") (pin "AB25") (pinfunction "DRAM_D56_AB25") (pintype "bidirectional"))
    )
    (net (code "86") (name "/DDR3_D57") (class "Default")
      (node (ref "JP10M") (pin "183") (pinfunction "DQ57_183") (pintype "bidirectional"))
      (node (ref "U100") (pin "AA21") (pinfunction "DRAM_D57_AA21") (pintype "bidirectional"))
    )
    (net (code "87") (name "/DDR3_D58") (class "Default")
      (node (ref "JP10M") (pin "191") (pinfunction "DQ58_191") (pintype "bidirectional"))
      (node (ref "U100") (pin "Y25") (pinfunction "DRAM_D58_Y25") (pintype "bidirectional"))
    )
    (net (code "88") (name "/DDR3_D59") (class "Default")
      (node (ref "JP10M") (pin "193") (pinfunction "DQ59_193") (pintype "bidirectional"))
      (node (ref "U100") (pin "AA23") (pinfunction "DRAM_D61_AA23") (pintype "bidirectional"))
    )
    (net (code "89") (name "/DDR3_D60") (class "Default")
      (node (ref "JP10M") (pin "180") (pinfunction "DQ60_180") (pintype "bidirectional"))
      (node (ref "U100") (pin "AB23") (pinfunction "DRAM_D60_AB23") (pintype "bidirectional"))
    )
    (net (code "90") (name "/DDR3_D61") (class "Default")
      (node (ref "JP10M") (pin "182") (pinfunction "DQ61_182") (pintype "bidirectional"))
      (node (ref "U100") (pin "Y22") (pinfunction "DRAM_D59_Y22") (pintype "bidirectional"))
    )
    (net (code "91") (name "/DDR3_D62") (class "Default")
      (node (ref "JP10M") (pin "192") (pinfunction "DQ62_192") (pintype "bidirectional"))
      (node (ref "U100") (pin "W25") (pinfunction "DRAM_D63_W25") (pintype "bidirectional"))
    )
    (net (code "92") (name "/DDR3_D63") (class "Default")
      (node (ref "JP10M") (pin "194") (pinfunction "DQ63_194") (pintype "bidirectional"))
      (node (ref "U100") (pin "Y23") (pinfunction "DRAM_D62_Y23") (pintype "bidirectional"))
    )
    (net (code "93") (name "/DDR3_DM0") (class "Default")
      (node (ref "JP10M") (pin "11") (pinfunction "DM0_11") (pintype "input"))
      (node (ref "U100") (pin "AC3") (pinfunction "DRAM_DQM0_AC3") (pintype "input"))
    )
    (net (code "94") (name "/DDR3_DM1") (class "Default")
      (node (ref "JP10M") (pin "28") (pinfunction "DM1_28") (pintype "input"))
      (node (ref "U100") (pin "AC6") (pinfunction "DRAM_DQM1_AC6") (pintype "input"))
    )
    (net (code "95") (name "/DDR3_DM2") (class "Default")
      (node (ref "JP10M") (pin "46") (pinfunction "DM2_46") (pintype "input"))
      (node (ref "U100") (pin "AB8") (pinfunction "DRAM_DQM2_AB8") (pintype "input"))
    )
    (net (code "96") (name "/DDR3_DM3") (class "Default")
      (node (ref "JP10M") (pin "63") (pinfunction "DM3_63") (pintype "input"))
      (node (ref "U100") (pin "AE10") (pinfunction "DRAM_DQM3_AE10") (pintype "input"))
    )
    (net (code "97") (name "/DDR3_DM4") (class "Default")
      (node (ref "JP10M") (pin "136") (pinfunction "DM4_136") (pintype "input"))
      (node (ref "U100") (pin "AB18") (pinfunction "DRAM_DQM4_AB18") (pintype "input"))
    )
    (net (code "98") (name "/DDR3_DM5") (class "Default")
      (node (ref "JP10M") (pin "153") (pinfunction "DM5_153") (pintype "input"))
      (node (ref "U100") (pin "AC20") (pinfunction "DRAM_DQM5_AC20") (pintype "input"))
    )
    (net (code "99") (name "/DDR3_DM6") (class "Default")
      (node (ref "JP10M") (pin "170") (pinfunction "DM6_170") (pintype "input"))
      (node (ref "U100") (pin "AD24") (pinfunction "DRAM_DQM6_AD24") (pintype "input"))
    )
    (net (code "100") (name "/DDR3_DM7") (class "Default")
      (node (ref "JP10M") (pin "187") (pinfunction "DM7_187") (pintype "input"))
      (node (ref "U100") (pin "Y21") (pinfunction "DRAM_DQM7_Y21") (pintype "input"))
    )
    (net (code "101") (name "/DDR3_DQS0_N") (class "Default")
      (node (ref "JP10M") (pin "10") (pinfunction "DQS0_N_10") (pintype "bidirectional"))
      (node (ref "U100") (pin "AD3") (pinfunction "DRAM_SDQS0_B_AD3") (pintype "bidirectional"))
    )
    (net (code "102") (name "/DDR3_DQS0_P") (class "Default")
      (node (ref "JP10M") (pin "12") (pinfunction "DQS0_P_12") (pintype "bidirectional"))
      (node (ref "U100") (pin "AE3") (pinfunction "DRAM_SDQS0_AE3") (pintype "bidirectional"))
    )
    (net (code "103") (name "/DDR3_DQS1_N") (class "Default")
      (node (ref "JP10M") (pin "27") (pinfunction "DQS1_N_27") (pintype "bidirectional"))
      (node (ref "U100") (pin "AE6") (pinfunction "DRAM_SDQS1_B_AE6") (pintype "bidirectional"))
    )
    (net (code "104") (name "/DDR3_DQS1_P") (class "Default")
      (node (ref "JP10M") (pin "29") (pinfunction "DQS1_P_29") (pintype "bidirectional"))
      (node (ref "U100") (pin "AD6") (pinfunction "DRAM_SDQS1_AD6") (pintype "bidirectional"))
    )
    (net (code "105") (name "/DDR3_DQS2_N") (class "Default")
      (node (ref "JP10M") (pin "45") (pinfunction "DQS2_N_45") (pintype "bidirectional"))
      (node (ref "U100") (pin "AE8") (pinfunction "DRAM_SDQS2_B_AE8") (pintype "bidirectional"))
    )
    (net (code "106") (name "/DDR3_DQS2_P") (class "Default")
      (node (ref "JP10M") (pin "47") (pinfunction "DQS2_P_47") (pintype "bidirectional"))
      (node (ref "U100") (pin "AD8") (pinfunction "DRAM_SDQS2_AD8") (pintype "bidirectional"))
    )
    (net (code "107") (name "/DDR3_DQS3_N") (class "Default")
      (node (ref "JP10M") (pin "62") (pinfunction "DQS3_N_62") (pintype "bidirectional"))
      (node (ref "U100") (pin "AB10") (pinfunction "DRAM_SDQS3_B_AB10") (pintype "bidirectional"))
    )
    (net (code "108") (name "/DDR3_DQS3_P") (class "Default")
      (node (ref "JP10M") (pin "64") (pinfunction "DQS3_P_64") (pintype "bidirectional"))
      (node (ref "U100") (pin "AC10") (pinfunction "DRAM_SDQS3_AC10") (pintype "bidirectional"))
    )
    (net (code "109") (name "/DDR3_DQS4_N") (class "Default")
      (node (ref "JP10M") (pin "135") (pinfunction "DQS4_N_135") (pintype "bidirectional"))
      (node (ref "U100") (pin "AE18") (pinfunction "DRAM_SDQS4_B_AE18") (pintype "bidirectional"))
    )
    (net (code "110") (name "/DDR3_DQS4_P") (class "Default")
      (node (ref "JP10M") (pin "137") (pinfunction "DQS4_P_137") (pintype "bidirectional"))
      (node (ref "U100") (pin "AD18") (pinfunction "DRAM_SDQS4_AD18") (pintype "bidirectional"))
    )
    (net (code "111") (name "/DDR3_DQS5_N") (class "Default")
      (node (ref "JP10M") (pin "152") (pinfunction "DQS5_N_152") (pintype "bidirectional"))
      (node (ref "U100") (pin "AE20") (pinfunction "DRAM_SDQS5_B_AE20") (pintype "bidirectional"))
    )
    (net (code "112") (name "/DDR3_DQS5_P") (class "Default")
      (node (ref "JP10M") (pin "154") (pinfunction "DQS5_P_154") (pintype "bidirectional"))
      (node (ref "U100") (pin "AD20") (pinfunction "DRAM_SDQS5_AD20") (pintype "bidirectional"))
    )
    (net (code "113") (name "/DDR3_DQS6_N") (class "Default")
      (node (ref "JP10M") (pin "169") (pinfunction "DQS6_N_169") (pintype "bidirectional"))
      (node (ref "U100") (pin "AE23") (pinfunction "DRAM_SDQS6_B_AE23") (pintype "bidirectional"))
    )
    (net (code "114") (name "/DDR3_DQS6_P") (class "Default")
      (node (ref "JP10M") (pin "171") (pinfunction "DQS6_P_171") (pintype "bidirectional"))
      (node (ref "U100") (pin "AD23") (pinfunction "DRAM_SDQS6_AD23") (pintype "bidirectional"))
    )
    (net (code "115") (name "/DDR3_DQS7_N") (class "Default")
      (node (ref "JP10M") (pin "186") (pinfunction "DQS7_N_186") (pintype "bidirectional"))
      (node (ref "U100") (pin "AA24") (pinfunction "DRAM_SDQS7_B_AA24") (pintype "bidirectional"))
    )
    (net (code "116") (name "/DDR3_DQS7_P") (class "Default")
      (node (ref "JP10M") (pin "188") (pinfunction "DQS7_P_188") (pintype "bidirectional"))
      (node (ref "U100") (pin "AA25") (pinfunction "DRAM_SDQS7_AA25") (pintype "bidirectional"))
    )
    (net (code "117") (name "/DDR3_EVENT_N") (class "Default")
      (node (ref "JP10M") (pin "198") (pinfunction "EVENT_N_198") (pintype "input"))
      (node (ref "R12M") (pin "2") (pinfunction "2_2") (pintype "passive"))
    )
    (net (code "118") (name "/DDR3_ODT0") (class "Default")
      (node (ref "JP10M") (pin "116") (pinfunction "ODT0_116") (pintype "input"))
      (node (ref "U100") (pin "AC16") (pinfunction "DRAM_SDODT0_AC16") (pintype "output"))
    )
    (net (code "119") (name "/DDR3_ODT1") (class "Default")
      (node (ref "JP10M") (pin "120") (pinfunction "ODT1_120") (pintype "input"))
      (node (ref "U100") (pin "AB17") (pinfunction "DRAM_SDODT1_AB17") (pintype "output"))
    )
    (net (code "120") (name "/DDR3_RAS") (class "Default")
      (node (ref "JP10M") (pin "110") (pinfunction "RAS_N_110") (pintype "input"))
      (node (ref "U100") (pin "AB15") (pinfunction "DRAM_RAS_AB15") (pintype "output"))
    )
    (net (code "121") (name "/DDR3_RESET") (class "Default")
      (node (ref "JP10M") (pin "30") (pinfunction "RESET_N_30") (pintype "input"))
      (node (ref "R10M") (pin "1") (pinfunction "1_1") (pintype "passive"))
      (node (ref "U100") (pin "Y6") (pinfunction "DRAM_RESET_Y6") (pintype "output"))
    )
    (net (code "122") (name "/DDR3_WE") (class "Default")
      (node (ref "JP10M") (pin "113") (pinfunction "WE_N_113") (pintype "input"))
      (node (ref "U100") (pin "AB16") (pinfunction "DRAM_SDWE_AB16") (pintype "output"))
    )
    (net (code "123") (name "/DDR3_ZQPAD") (class "Default")
      (node (ref "R11M") (pin "1") (pinfunction "1_1") (pintype "passive"))
      (node (ref "U100") (pin "AE17") (pinfunction "ZQPAD_AE17") (pintype "input"))
    )
    (net (code "124") (name "/SMB_SCL") (class "Default")
      (node (ref "JP10M") (pin "202") (pinfunction "SCL_202") (pintype "input"))
    )
    (net (code "125") (name "/SMB_SDA") (class "Default")
      (node (ref "JP10M") (pin "200") (pinfunction "SDA_200") (pintype "bidirectional"))
    )
    (net (code "126") (name "/VTT_VCNTL") (class "Default")
      (node (ref "C54M") (pin "1") (pinfunction "1_1") (pintype "passive"))
      (node (ref "R13M") (pin "2") (pinfunction "2_2") (pintype "passive"))
      (node (ref "U10M") (pin "6") (pinfunction "VCNTL_6") (pintype "passive"))
    )
    (net (code "127") (name "GND") (class "Default")
      (node (ref "C10M") (pin "2") (pinfunction "2_2") (pintype "passive"))
      (node (ref "C11M") (pin "2") (pinfunction "2_2") (pintype "passive"))
      (node (ref "C14M") (pin "2") (pinfunction "2_2") (pintype "passive"))
      (node (ref "C15M") (pin "2") (pinfunction "2_2") (pintype "passive"))
      (node (ref "C16M") (pin "2") (pinfunction "2_2") (pintype "passive"))
      (node (ref "C17M") (pin "2") (pinfunction "2_2") (pintype "passive"))
      (node (ref "C18M") (pin "2") (pinfunction "2_2") (pintype "passive"))
      (node (ref "C19M") (pin "2") (pinfunction "2_2") (pintype "passive"))
      (node (ref "C20M") (pin "2") (pinfunction "2_2") (pintype "passive"))
      (node (ref "C21M") (pin "2") (pinfunction "2_2") (pintype "passive"))
      (node (ref "C22M") (pin "2") (pinfunction "2_2") (pintype "passive"))
      (node (ref "C23M") (pin "2") (pinfunction "2_2") (pintype "passive"))
      (node (ref "C24M") (pin "2") (pinfunction "2_2") (pintype "passive"))
      (node (ref "C25M") (pin "2") (pinfunction "2_2") (pintype "passive"))
      (node (ref "C26M") (pin "2") (pinfunction "2_2") (pintype "passive"))
      (node (ref "C27M") (pin "2") (pinfunction "2_2") (pintype "passive"))
      (node (ref "C28M") (pin "2") (pinfunction "2_2") (pintype "passive"))
      (node (ref "C29M") (pin "2") (pinfunction "2_2") (pintype "passive"))
      (node (ref "C30M") (pin "2") (pinfunction "2_2") (pintype "passive"))
      (node (ref "C31M") (pin "2") (pinfunction "2_2") (pintype "passive"))
      (node (ref "C32M") (pin "2") (pinfunction "2_2") (pintype "passive"))
      (node (ref "C33M") (pin "2") (pinfunction "2_2") (pintype "passive"))
      (node (ref "C34M") (pin "2") (pinfunction "2_2") (pintype "passive"))
      (node (ref "C35M") (pin "2") (pinfunction "2_2") (pintype "passive"))
      (node (ref "C36M") (pin "2") (pinfunction "2_2") (pintype "passive"))
      (node (ref "C37M") (pin "2") (pinfunction "2_2") (pintype "passive"))
      (node (ref "C38M") (pin "2") (pinfunction "2_2") (pintype "passive"))
      (node (ref "C39M") (pin "2") (pinfunction "2_2") (pintype "passive"))
      (node (ref "C40M") (pin "2") (pinfunction "2_2") (pintype "passive"))
      (node (ref "C41M") (pin "2") (pinfunction "2_2") (pintype "passive"))
      (node (ref "C42M") (pin "2") (pinfunction "2_2") (pintype "passive"))
      (node (ref "C43M") (pin "2") (pinfunction "2_2") (pintype "passive"))
      (node (ref "C44M") (pin "2") (pinfunction "2_2") (pintype "passive"))
      (node (ref "C45M") (pin "2") (pinfunction "2_2") (pintype "passive"))
      (node (ref "C46M") (pin "2") (pinfunction "2_2") (pintype "passive"))
      (node (ref "C47M") (pin "2") (pinfunction "2_2") (pintype "passive"))
      (node (ref "C48M") (pin "2") (pinfunction "2_2") (pintype "passive"))
      (node (ref "C49M") (pin "2") (pinfunction "2_2") (pintype "passive"))
      (node (ref "C50M") (pin "2") (pinfunction "2_2") (pintype "passive"))
      (node (ref "C51M") (pin "2") (pinfunction "2_2") (pintype "passive"))
      (node (ref "C52M") (pin "2") (pinfunction "2_2") (pintype "passive"))
      (node (ref "C53M") (pin "2") (pinfunction "2_2") (pintype "passive"))
      (node (ref "C54M") (pin "2") (pinfunction "2_2") (pintype "passive"))
      (node (ref "C55M") (pin "2") (pinfunction "2_2") (pintype "passive"))
      (node (ref "C56M") (pin "2") (pinfunction "2_2") (pintype "passive"))
      (node (ref "JP10M") (pin "127") (pinfunction "VSS_127") (pintype "power_in"))
      (node (ref "JP10M") (pin "128") (pinfunction "VSS_128") (pintype "power_in"))
      (node (ref "JP10M") (pin "13") (pinfunction "VSS_13") (pintype "power_in"))
      (node (ref "JP10M") (pin "133") (pinfunction "VSS_133") (pintype "power_in"))
      (node (ref "JP10M") (pin "134") (pinfunction "VSS_134") (pintype "power_in"))
      (node (ref "JP10M") (pin "138") (pinfunction "VSS_138") (pintype "power_in"))
      (node (ref "JP10M") (pin "139") (pinfunction "VSS_139") (pintype "power_in"))
      (node (ref "JP10M") (pin "14") (pinfunction "VSS_14") (pintype "power_in"))
      (node (ref "JP10M") (pin "144") (pinfunction "VSS_144") (pintype "power_in"))
      (node (ref "JP10M") (pin "145") (pinfunction "VSS_145") (pintype "power_in"))
      (node (ref "JP10M") (pin "150") (pinfunction "VSS_150") (pintype "power_in"))
      (node (ref "JP10M") (pin "151") (pinfunction "VSS_151") (pintype "power_in"))
      (node (ref "JP10M") (pin "155") (pinfunction "VSS_155") (pintype "power_in"))
      (node (ref "JP10M") (pin "156") (pinfunction "VSS_156") (pintype "power_in"))
      (node (ref "JP10M") (pin "161") (pinfunction "VSS_161") (pintype "power_in"))
      (node (ref "JP10M") (pin "162") (pinfunction "VSS_162") (pintype "power_in"))
      (node (ref "JP10M") (pin "167") (pinfunction "VSS_167") (pintype "power_in"))
      (node (ref "JP10M") (pin "168") (pinfunction "VSS_168") (pintype "power_in"))
      (node (ref "JP10M") (pin "172") (pinfunction "VSS_172") (pintype "power_in"))
      (node (ref "JP10M") (pin "173") (pinfunction "VSS_173") (pintype "power_in"))
      (node (ref "JP10M") (pin "178") (pinfunction "VSS_178") (pintype "power_in"))
      (node (ref "JP10M") (pin "179") (pinfunction "VSS_179") (pintype "power_in"))
      (node (ref "JP10M") (pin "184") (pinfunction "VSS_184") (pintype "power_in"))
      (node (ref "JP10M") (pin "185") (pinfunction "VSS_185") (pintype "power_in"))
      (node (ref "JP10M") (pin "189") (pinfunction "VSS_189") (pintype "power_in"))
      (node (ref "JP10M") (pin "19") (pinfunction "VSS_19") (pintype "power_in"))
      (node (ref "JP10M") (pin "190") (pinfunction "VSS_190") (pintype "power_in"))
      (node (ref "JP10M") (pin "195") (pinfunction "VSS_195") (pintype "power_in"))
      (node (ref "JP10M") (pin "196") (pinfunction "VSS_196") (pintype "power_in"))
      (node (ref "JP10M") (pin "197") (pinfunction "SA0_197") (pintype "input"))
      (node (ref "JP10M") (pin "2") (pinfunction "VSS_2") (pintype "power_in"))
      (node (ref "JP10M") (pin "20") (pinfunction "VSS_20") (pintype "power_in"))
      (node (ref "JP10M") (pin "201") (pinfunction "SA1_201") (pintype "input"))
      (node (ref "JP10M") (pin "25") (pinfunction "VSS_25") (pintype "power_in"))
      (node (ref "JP10M") (pin "26") (pinfunction "VSS_26") (pintype "power_in"))
      (node (ref "JP10M") (pin "3") (pinfunction "VSS_3") (pintype "power_in"))
      (node (ref "JP10M") (pin "31") (pinfunction "VSS_31") (pintype "power_in"))
      (node (ref "JP10M") (pin "32") (pinfunction "VSS_32") (pintype "power_in"))
      (node (ref "JP10M") (pin "37") (pinfunction "VSS_37") (pintype "power_in"))
      (node (ref "JP10M") (pin "38") (pinfunction "VSS_38") (pintype "power_in"))
      (node (ref "JP10M") (pin "43") (pinfunction "VSS_43") (pintype "bidirectional"))
      (node (ref "JP10M") (pin "44") (pinfunction "VSS_44") (pintype "bidirectional"))
      (node (ref "JP10M") (pin "48") (pinfunction "VSS_48") (pintype "power_in"))
      (node (ref "JP10M") (pin "49") (pinfunction "VSS_49") (pintype "power_in"))
      (node (ref "JP10M") (pin "54") (pinfunction "VSS_54") (pintype "power_in"))
      (node (ref "JP10M") (pin "55") (pinfunction "VSS_55") (pintype "power_in"))
      (node (ref "JP10M") (pin "60") (pinfunction "VSS_60") (pintype "power_in"))
      (node (ref "JP10M") (pin "61") (pinfunction "VSS_61") (pintype "power_in"))
      (node (ref "JP10M") (pin "65") (pinfunction "VSS_65") (pintype "power_in"))
      (node (ref "JP10M") (pin "66") (pinfunction "VSS_66") (pintype "power_in"))
      (node (ref "JP10M") (pin "71") (pinfunction "VSS_71") (pintype "power_in"))
      (node (ref "JP10M") (pin "72") (pinfunction "VSS_72") (pintype "power_in"))
      (node (ref "JP10M") (pin "8") (pinfunction "VSS_8") (pintype "power_in"))
      (node (ref "JP10M") (pin "9") (pinfunction "VSS_9") (pintype "power_in"))
      (node (ref "R10M") (pin "2") (pinfunction "2_2") (pintype "passive"))
      (node (ref "R11M") (pin "2") (pinfunction "2_2") (pintype "passive"))
      (node (ref "R14M") (pin "2") (pinfunction "2_2") (pintype "passive"))
      (node (ref "U10M") (pin "2") (pinfunction "GND_2") (pintype "power_in"))
      (node (ref "U10M") (pin "9") (pinfunction "GND_9") (pintype "power_in"))
    )
    (net (code "128") (name "Net-(U10M-VIN)") (class "Default")
      (node (ref "C55M") (pin "1") (pinfunction "1_1") (pintype "passive"))
      (node (ref "R15M") (pin "2") (pinfunction "2_2") (pintype "passive"))
      (node (ref "R16M") (pin "2") (pinfunction "2_2") (pintype "passive"))
      (node (ref "U10M") (pin "1") (pinfunction "VIN_1") (pintype "power_in"))
    )
    (net (code "129") (name "P0.75V_DDR3_VTT") (class "Default")
      (node (ref "C18M") (pin "1") (pinfunction "1_1") (pintype "passive"))
      (node (ref "C19M") (pin "1") (pinfunction "1_1") (pintype "passive"))
      (node (ref "C20M") (pin "1") (pinfunction "1_1") (pintype "passive"))
      (node (ref "C56M") (pin "1") (pinfunction "1_1") (pintype "passive"))
      (node (ref "JP10M") (pin "203") (pinfunction "VTT_203") (pintype "power_in"))
      (node (ref "JP10M") (pin "204") (pinfunction "VTT_204") (pintype "power_in"))
      (node (ref "R14M") (pin "1") (pinfunction "1_1") (pintype "passive"))
      (node (ref "U10M") (pin "4") (pinfunction "VOUT_4") (pintype "power_in"))
    )
    (net (code "130") (name "P0.75V_REFDDR") (class "Default")
      (node (ref "C10M") (pin "1") (pinfunction "1_1") (pintype "passive"))
      (node (ref "C11M") (pin "1") (pinfunction "1_1") (pintype "passive"))
      (node (ref "C14M") (pin "1") (pinfunction "1_1") (pintype "passive"))
      (node (ref "C15M") (pin "1") (pinfunction "1_1") (pintype "passive"))
      (node (ref "C16M") (pin "1") (pinfunction "1_1") (pintype "passive"))
      (node (ref "C40M") (pin "1") (pinfunction "1_1") (pintype "passive"))
      (node (ref "JP10M") (pin "1") (pinfunction "VREFDQ_1") (pintype "power_in"))
      (node (ref "JP10M") (pin "126") (pinfunction "VREFCA_126") (pintype "power_in"))
      (node (ref "U100") (pin "AC2") (pinfunction "DRAM_VREF_AC2") (pintype "power_in"))
      (node (ref "U10M") (pin "3") (pinfunction "REFEN_3") (pintype "passive"))
    )
    (net (code "131") (name "P1.5V_DDR_SW3") (class "Default")
      (node (ref "C21M") (pin "1") (pinfunction "1_1") (pintype "passive"))
      (node (ref "C22M") (pin "1") (pinfunction "1_1") (pintype "passive"))
      (node (ref "C23M") (pin "1") (pinfunction "1_1") (pintype "passive"))
      (node (ref "C24M") (pin "1") (pinfunction "1_1") (pintype "passive"))
      (node (ref "C25M") (pin "1") (pinfunction "1_1") (pintype "passive"))
      (node (ref "C26M") (pin "1") (pinfunction "1_1") (pintype "passive"))
      (node (ref "C27M") (pin "1") (pinfunction "1_1") (pintype "passive"))
      (node (ref "C28M") (pin "1") (pinfunction "1_1") (pintype "passive"))
      (node (ref "C29M") (pin "1") (pinfunction "1_1") (pintype "passive"))
      (node (ref "C30M") (pin "1") (pinfunction "1_1") (pintype "passive"))
      (node (ref "C31M") (pin "1") (pinfunction "1_1") (pintype "passive"))
      (node (ref "C32M") (pin "1") (pinfunction "1_1") (pintype "passive"))
      (node (ref "C33M") (pin "1") (pinfunction "1_1") (pintype "passive"))
      (node (ref "C34M") (pin "1") (pinfunction "1_1") (pintype "passive"))
      (node (ref "C35M") (pin "1") (pinfunction "1_1") (pintype "passive"))
      (node (ref "C36M") (pin "1") (pinfunction "1_1") (pintype "passive"))
      (node (ref "C37M") (pin "1") (pinfunction "1_1") (pintype "passive"))
      (node (ref "C38M") (pin "1") (pinfunction "1_1") (pintype "passive"))
      (node (ref "C39M") (pin "1") (pinfunction "1_1") (pintype "passive"))
      (node (ref "C41M") (pin "1") (pinfunction "1_1") (pintype "passive"))
      (node (ref "C42M") (pin "1") (pinfunction "1_1") (pintype "passive"))
      (node (ref "C43M") (pin "1") (pinfunction "1_1") (pintype "passive"))
      (node (ref "C44M") (pin "1") (pinfunction "1_1") (pintype "passive"))
      (node (ref "C45M") (pin "1") (pinfunction "1_1") (pintype "passive"))
      (node (ref "C46M") (pin "1") (pinfunction "1_1") (pintype "passive"))
      (node (ref "C47M") (pin "1") (pinfunction "1_1") (pintype "passive"))
      (node (ref "C48M") (pin "1") (pinfunction "1_1") (pintype "passive"))
      (node (ref "C49M") (pin "1") (pinfunction "1_1") (pintype "passive"))
      (node (ref "C50M") (pin "1") (pinfunction "1_1") (pintype "passive"))
      (node (ref "C51M") (pin "1") (pinfunction "1_1") (pintype "passive"))
      (node (ref "C52M") (pin "1") (pinfunction "1_1") (pintype "passive"))
      (node (ref "C53M") (pin "1") (pinfunction "1_1") (pintype "passive"))
      (node (ref "JP10M") (pin "100") (pinfunction "VDD_100") (pintype "power_in"))
      (node (ref "JP10M") (pin "105") (pinfunction "VDD_105") (pintype "power_in"))
      (node (ref "JP10M") (pin "106") (pinfunction "VDD_106") (pintype "power_in"))
      (node (ref "JP10M") (pin "111") (pinfunction "VDD_111") (pintype "power_in"))
      (node (ref "JP10M") (pin "112") (pinfunction "VDD_112") (pintype "power_in"))
      (node (ref "JP10M") (pin "117") (pinfunction "VDD_117") (pintype "power_in"))
      (node (ref "JP10M") (pin "118") (pinfunction "VDD_118") (pintype "power_in"))
      (node (ref "JP10M") (pin "123") (pinfunction "VDD_123") (pintype "power_in"))
      (node (ref "JP10M") (pin "124") (pinfunction "VDD_124") (pintype "power_in"))
      (node (ref "JP10M") (pin "75") (pinfunction "VDD_75") (pintype "power_in"))
      (node (ref "JP10M") (pin "76") (pinfunction "VDD_76") (pintype "power_in"))
      (node (ref "JP10M") (pin "81") (pinfunction "VDD_81") (pintype "power_in"))
      (node (ref "JP10M") (pin "82") (pinfunction "VDD_82") (pintype "power_in"))
      (node (ref "JP10M") (pin "87") (pinfunction "VDD_87") (pintype "power_in"))
      (node (ref "JP10M") (pin "88") (pinfunction "VDD_88") (pintype "power_in"))
      (node (ref "JP10M") (pin "93") (pinfunction "VDD_93") (pintype "power_in"))
      (node (ref "JP10M") (pin "94") (pinfunction "VDD_94") (pintype "power_in"))
      (node (ref "JP10M") (pin "99") (pinfunction "VDD_99") (pintype "power_in"))
      (node (ref "R15M") (pin "1") (pinfunction "1_1") (pintype "passive"))
      (node (ref "U100") (pin "R18") (pinfunction "NVCC_DRAM_1_R18") (pintype "power_in"))
      (node (ref "U100") (pin "T18") (pinfunction "NVCC_DRAM_2_T18") (pintype "power_in"))
      (node (ref "U100") (pin "U18") (pinfunction "NVCC_DRAM_3_U18") (pintype "power_in"))
      (node (ref "U100") (pin "V10") (pinfunction "NVCC_DRAM_4_V10") (pintype "power_in"))
      (node (ref "U100") (pin "V11") (pinfunction "NVCC_DRAM_5_V11") (pintype "power_in"))
      (node (ref "U100") (pin "V12") (pinfunction "NVCC_DRAM_6_V12") (pintype "power_in"))
      (node (ref "U100") (pin "V13") (pinfunction "NVCC_DRAM_7_V13") (pintype "power_in"))
      (node (ref "U100") (pin "V14") (pinfunction "NVCC_DRAM_8_V14") (pintype "power_in"))
      (node (ref "U100") (pin "V15") (pinfunction "NVCC_DRAM_9_V15") (pintype "power_in"))
      (node (ref "U100") (pin "V16") (pinfunction "NVCC_DRAM_10_V16") (pintype "power_in"))
      (node (ref "U100") (pin "V17") (pinfunction "NVCC_DRAM_11_V17") (pintype "power_in"))
      (node (ref "U100") (pin "V18") (pinfunction "NVCC_DRAM_12_V18") (pintype "power_in"))
      (node (ref "U100") (pin "V9") (pinfunction "NVCC_DRAM_13_V9") (pintype "power_in"))
    )
    (net (code "132") (name "P1.8V_SW4") (class "Default")
      (node (ref "R16M") (pin "1") (pinfunction "1_1") (pintype "passive"))
    )
    (net (code "133") (name "P3.3V_DELAYED") (class "Default")
      (node (ref "C17M") (pin "1") (pinfunction "1_1") (pintype "passive"))
      (node (ref "JP10M") (pin "199") (pinfunction "VDDSPD_199") (pintype "power_in"))
      (node (ref "R12M") (pin "1") (pinfunction "1_1") (pintype "passive"))
    )
    (net (code "134") (name "P5.0V") (class "Default")
      (node (ref "R13M") (pin "1") (pinfunction "1_1") (pintype "passive"))
    )
  )
)
